# SX70_Flash_Tester.net
KiCad netlist of a schematic drawn in EAGLE
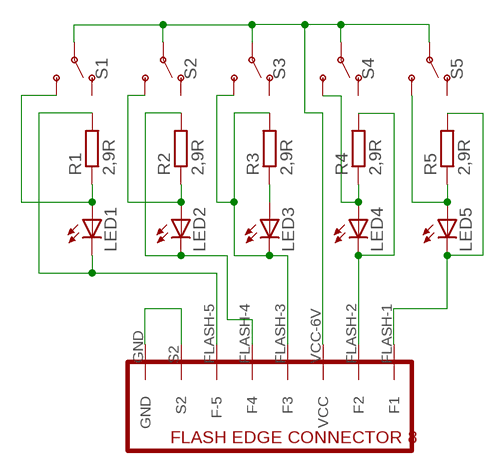
[diagram p0: schematic, sheet 1]

(export (version "E")
  (design (tool "Eeschema 10.0.6"))
  (components
    (comp (ref "FLASH-TESTER")
      (value "SX70-FLASH-EDGE8-MALE")
      (footprint "eagle-import:SX70-FLASH-EDGE8")
      (libsource (lib "eagle-import") (part "SX70-FLASH-EDGE8-MALE"))
    )
    (comp (ref "LED1")
      (value "LED3MM")
      (footprint "eagle-import:LED3MM")
      (libsource (lib "eagle-import") (part "LED3MM"))
    )
    (comp (ref "LED2")
      (value "LED3MM")
      (footprint "eagle-import:LED3MM")
      (libsource (lib "eagle-import") (part "LED3MM"))
    )
    (comp (ref "LED3")
      (value "LED3MM")
      (footprint "eagle-import:LED3MM")
      (libsource (lib "eagle-import") (part "LED3MM"))
    )
    (comp (ref "LED4")
      (value "LED3MM")
      (footprint "eagle-import:LED3MM")
      (libsource (lib "eagle-import") (part "LED3MM"))
    )
    (comp (ref "LED5")
      (value "LED3MM")
      (footprint "eagle-import:LED3MM")
      (libsource (lib "eagle-import") (part "LED3MM"))
    )
    (comp (ref "R1")
      (value "2,9R")
      (footprint "eagle-import:0204_7")
      (libsource (lib "eagle-import") (part "R-EU_0204/7"))
    )
    (comp (ref "R2")
      (value "2,9R")
      (footprint "eagle-import:0204_7")
      (libsource (lib "eagle-import") (part "R-EU_0204/7"))
    )
    (comp (ref "R3")
      (value "2,9R")
      (footprint "eagle-import:0204_7")
      (libsource (lib "eagle-import") (part "R-EU_0204/7"))
    )
    (comp (ref "R4")
      (value "2,9R")
      (footprint "eagle-import:0204_7")
      (libsource (lib "eagle-import") (part "R-EU_0204/7"))
    )
    (comp (ref "R5")
      (value "2,9R")
      (footprint "eagle-import:0204_7")
      (libsource (lib "eagle-import") (part "R-EU_0204/7"))
    )
    (comp (ref "S1")
      (value "SWITCH-SPDT-PTH-11.6X4.0MM-LOCK")
      (footprint "eagle-import:SWITCH_SPDT_PTH_11.6X4.0MM_LOCK")
      (libsource (lib "eagle-import") (part "SWITCH-SPDT-PTH-11.6X4.0MM-LOCK"))
    )
    (comp (ref "S2")
      (value "SWITCH-SPDT-PTH-11.6X4.0MM-LOCK")
      (footprint "eagle-import:SWITCH_SPDT_PTH_11.6X4.0MM_LOCK")
      (libsource (lib "eagle-import") (part "SWITCH-SPDT-PTH-11.6X4.0MM-LOCK"))
    )
    (comp (ref "S3")
      (value "SWITCH-SPDT-PTH-11.6X4.0MM-LOCK")
      (footprint "eagle-import:SWITCH_SPDT_PTH_11.6X4.0MM_LOCK")
      (libsource (lib "eagle-import") (part "SWITCH-SPDT-PTH-11.6X4.0MM-LOCK"))
    )
    (comp (ref "S4")
      (value "SWITCH-SPDT-PTH-11.6X4.0MM-LOCK")
      (footprint "eagle-import:SWITCH_SPDT_PTH_11.6X4.0MM_LOCK")
      (libsource (lib "eagle-import") (part "SWITCH-SPDT-PTH-11.6X4.0MM-LOCK"))
    )
    (comp (ref "S5")
      (value "SWITCH-SPDT-PTH-11.6X4.0MM-LOCK")
      (footprint "eagle-import:SWITCH_SPDT_PTH_11.6X4.0MM_LOCK")
      (libsource (lib "eagle-import") (part "SWITCH-SPDT-PTH-11.6X4.0MM-LOCK"))
    )
  )
  (nets
    (net (code "1") (name "Net-(FLASH-TESTER-F-5)") (class "Default")
      (node (ref "FLASH-TESTER") (pin "FLASH-5") (pinfunction "F-5_FLASH-5") (pintype "bidirectional"))
      (node (ref "LED1") (pin "K") (pinfunction "C_K") (pintype "passive"))
      (node (ref "R1") (pin "2") (pinfunction "2_2") (pintype "passive"))
    )
    (net (code "2") (name "Net-(FLASH-TESTER-F1)") (class "Default")
      (node (ref "FLASH-TESTER") (pin "FLASH-1") (pinfunction "F1_FLASH-1") (pintype "bidirectional"))
      (node (ref "LED5") (pin "K") (pinfunction "C_K") (pintype "passive"))
      (node (ref "R5") (pin "2") (pinfunction "2_2") (pintype "passive"))
    )
    (net (code "3") (name "Net-(FLASH-TESTER-F2)") (class "Default")
      (node (ref "FLASH-TESTER") (pin "FLASH-2") (pinfunction "F2_FLASH-2") (pintype "bidirectional"))
      (node (ref "LED4") (pin "K") (pinfunction "C_K") (pintype "passive"))
      (node (ref "R4") (pin "2") (pinfunction "2_2") (pintype "passive"))
    )
    (net (code "4") (name "Net-(FLASH-TESTER-F3)") (class "Default")
      (node (ref "FLASH-TESTER") (pin "FLASH-3") (pinfunction "F3_FLASH-3") (pintype "bidirectional"))
      (node (ref "LED3") (pin "K") (pinfunction "C_K") (pintype "passive"))
      (node (ref "R3") (pin "2") (pinfunction "2_2") (pintype "passive"))
      (node (ref "S3") (pin "3") (pinfunction "S_3") (pintype "passive"))
    )
    (net (code "5") (name "Net-(FLASH-TESTER-F4)") (class "Default")
      (node (ref "FLASH-TESTER") (pin "FLASH-4") (pinfunction "F4_FLASH-4") (pintype "bidirectional"))
      (node (ref "LED2") (pin "K") (pinfunction "C_K") (pintype "passive"))
      (node (ref "R2") (pin "2") (pinfunction "2_2") (pintype "passive"))
    )
    (net (code "6") (name "Net-(FLASH-TESTER-PadGND)") (class "Default")
      (node (ref "FLASH-TESTER") (pin "GND") (pinfunction "GND_GND") (pintype "bidirectional"))
      (node (ref "FLASH-TESTER") (pin "S2") (pinfunction "S2_S2") (pintype "bidirectional"))
    )
    (net (code "7") (name "Net-(FLASH-TESTER-VCC)") (class "Default")
      (node (ref "FLASH-TESTER") (pin "VCC-6V") (pinfunction "VCC_VCC-6V") (pintype "bidirectional"))
      (node (ref "S1") (pin "2") (pinfunction "P_2") (pintype "passive"))
      (node (ref "S2") (pin "2") (pinfunction "P_2") (pintype "passive"))
      (node (ref "S3") (pin "2") (pinfunction "P_2") (pintype "passive"))
      (node (ref "S4") (pin "2") (pinfunction "P_2") (pintype "passive"))
      (node (ref "S5") (pin "2") (pinfunction "P_2") (pintype "passive"))
    )
    (net (code "8") (name "Net-(LED3-PadA)") (class "Default")
      (node (ref "LED3") (pin "A") (pinfunction "A_A") (pintype "passive"))
      (node (ref "R3") (pin "1") (pinfunction "1_1") (pintype "passive"))
    )
    (net (code "9") (name "Net-(S1-S)") (class "Default")
      (node (ref "LED1") (pin "A") (pinfunction "A_A") (pintype "passive"))
      (node (ref "R1") (pin "1") (pinfunction "1_1") (pintype "passive"))
      (node (ref "S1") (pin "3") (pinfunction "S_3") (pintype "passive"))
    )
    (net (code "10") (name "Net-(S2-S)") (class "Default")
      (node (ref "LED2") (pin "A") (pinfunction "A_A") (pintype "passive"))
      (node (ref "R2") (pin "1") (pinfunction "1_1") (pintype "passive"))
      (node (ref "S2") (pin "3") (pinfunction "S_3") (pintype "passive"))
    )
    (net (code "11") (name "Net-(S4-S)") (class "Default")
      (node (ref "LED4") (pin "A") (pinfunction "A_A") (pintype "passive"))
      (node (ref "R4") (pin "1") (pinfunction "1_1") (pintype "passive"))
      (node (ref "S4") (pin "3") (pinfunction "S_3") (pintype "passive"))
    )
    (net (code "12") (name "Net-(S5-S)") (class "Default")
      (node (ref "LED5") (pin "A") (pinfunction "A_A") (pintype "passive"))
      (node (ref "R5") (pin "1") (pinfunction "1_1") (pintype "passive"))
      (node (ref "S5") (pin "3") (pinfunction "S_3") (pintype "passive"))
    )
    (net (code "13") (name "unconnected-(S1-O-Pad1)") (class "Default")
      (node (ref "S1") (pin "1") (pinfunction "O_1") (pintype "passive"))
    )
    (net (code "14") (name "unconnected-(S2-O-Pad1)") (class "Default")
      (node (ref "S2") (pin "1") (pinfunction "O_1") (pintype "passive"))
    )
    (net (code "15") (name "unconnected-(S3-O-Pad1)") (class "Default")
      (node (ref "S3") (pin "1") (pinfunction "O_1") (pintype "passive"))
    )
    (net (code "16") (name "unconnected-(S4-O-Pad1)") (class "Default")
      (node (ref "S4") (pin "1") (pinfunction "O_1") (pintype "passive"))
    )
    (net (code "17") (name "unconnected-(S5-O-Pad1)") (class "Default")
      (node (ref "S5") (pin "1") (pinfunction "O_1") (pintype "passive"))
    )
  )
)
